# Grace.net
KiCad netlist of a schematic drawn in Altium Designer
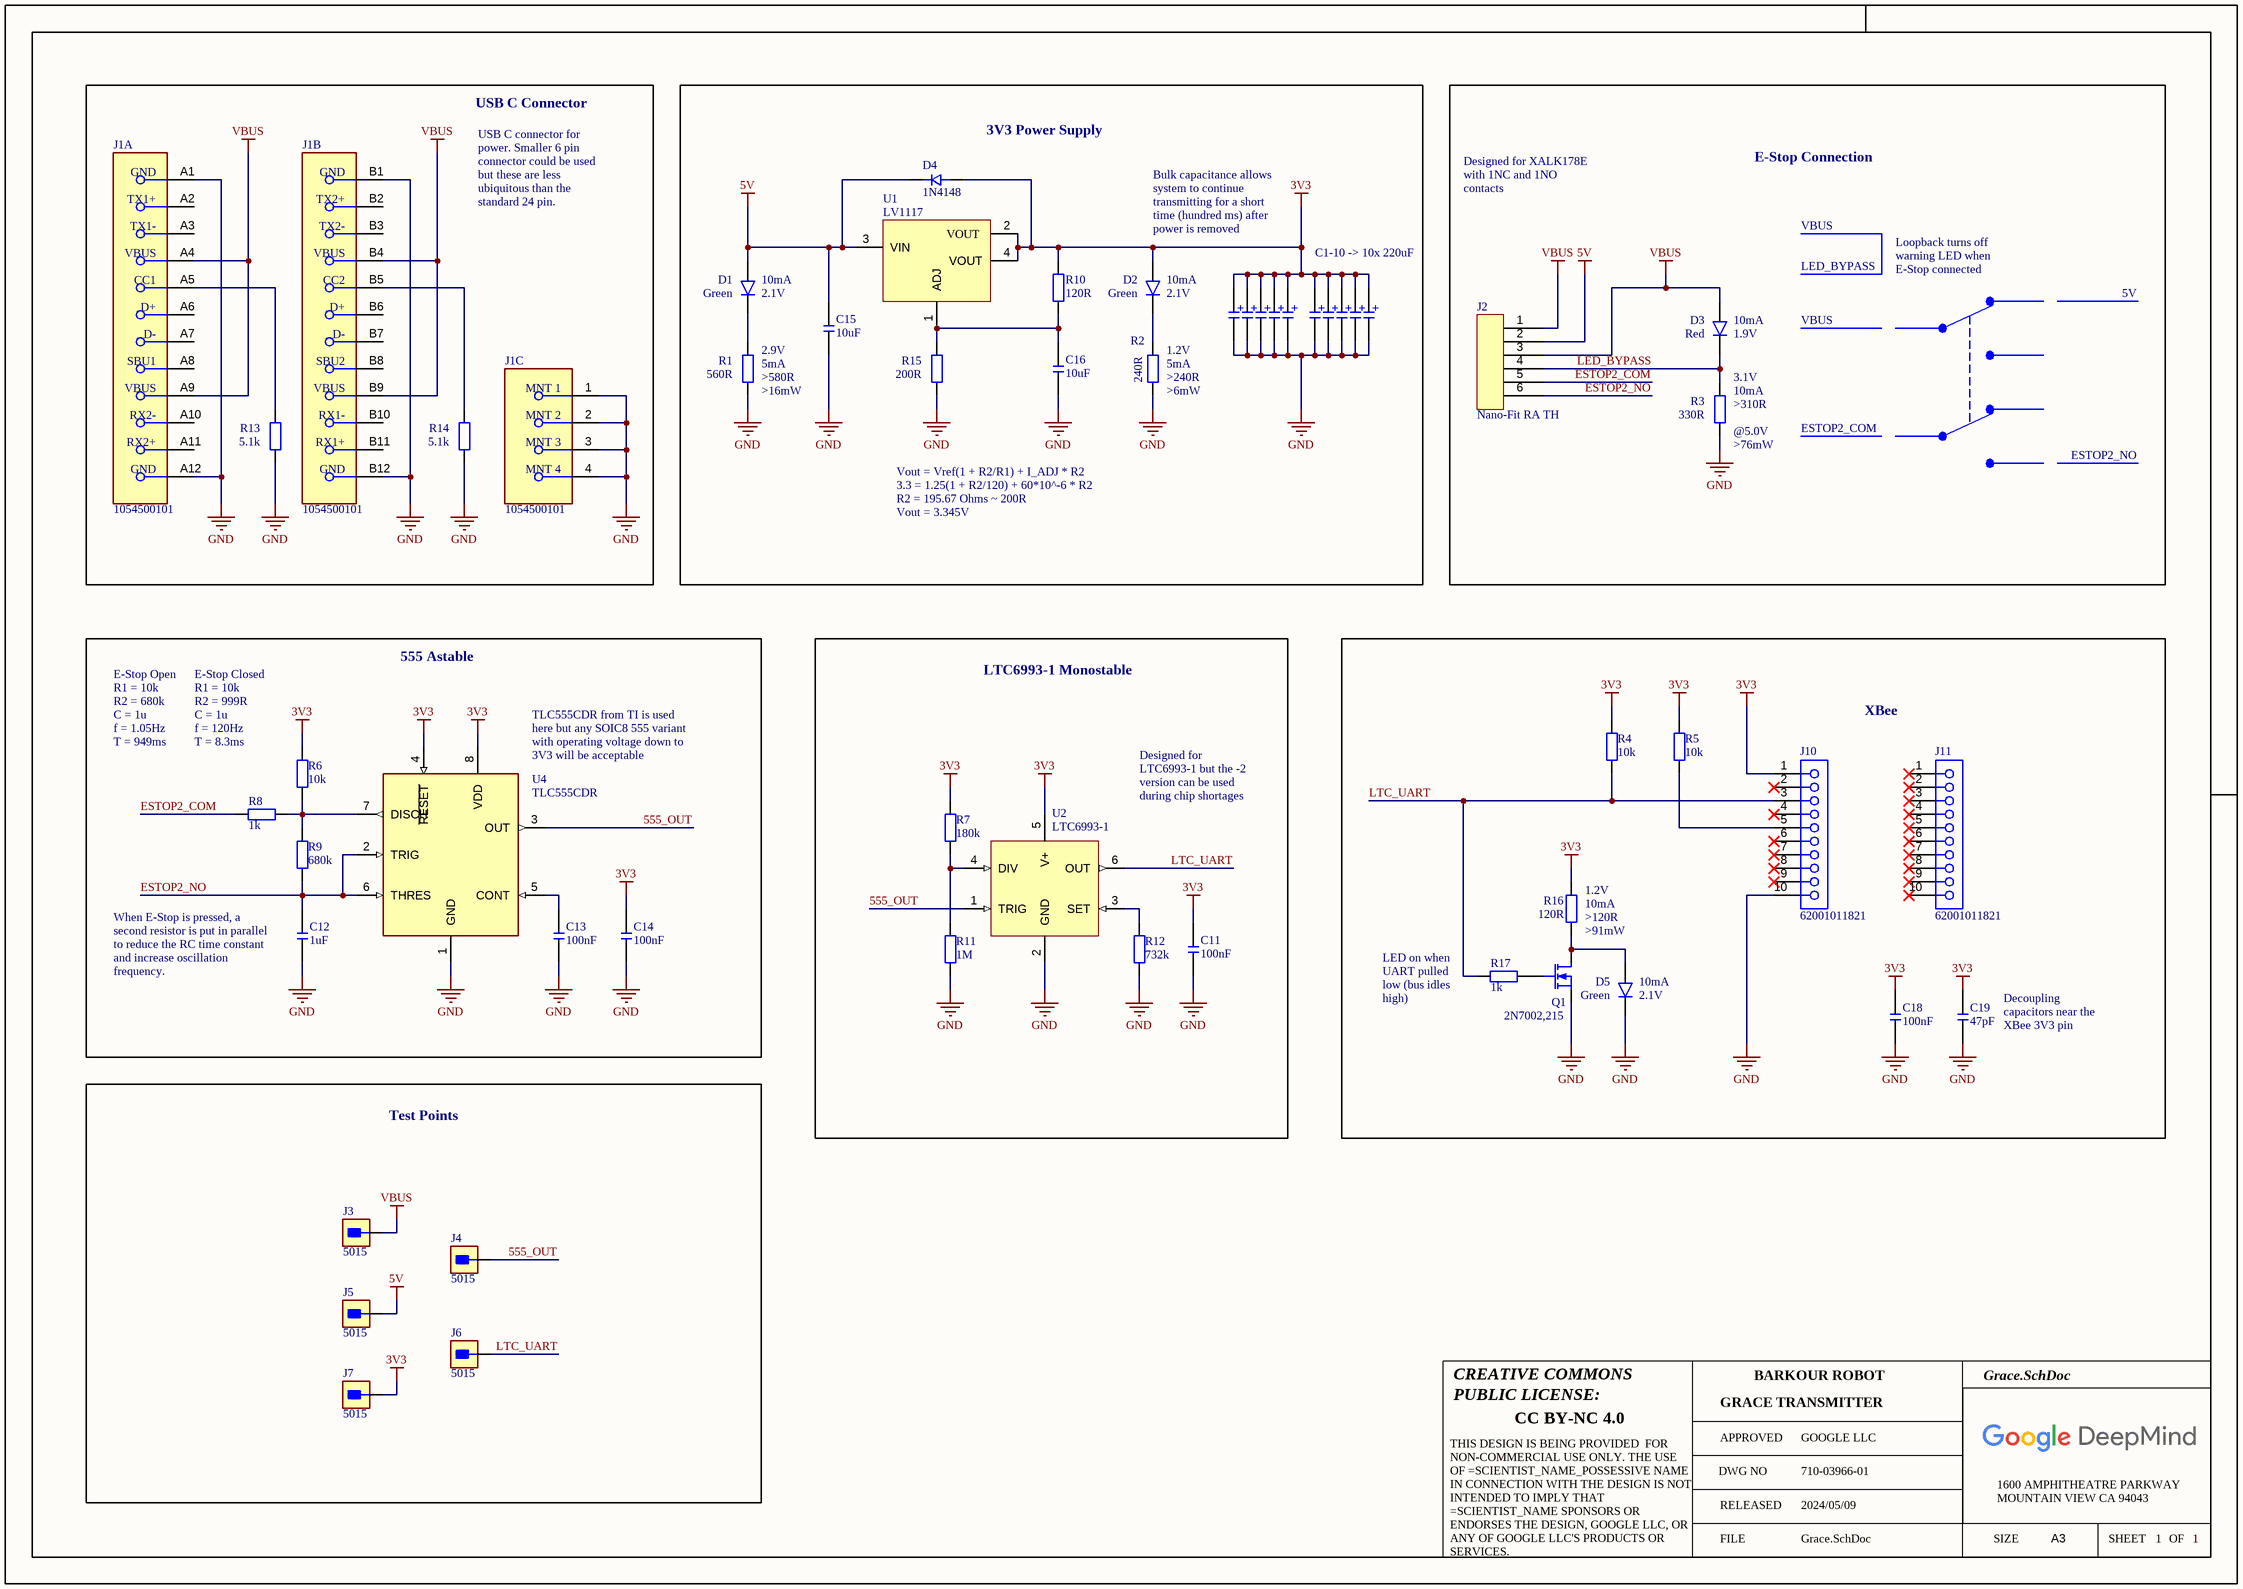
[diagram p0: Grace.SchDoc]

(export (version "E")
  (design (tool "Eeschema 10.0.6"))
  (components
    (comp (ref "C1")
      (value "220uF")
      (footprint "CAP ALSMD 6.6MM H7.7MM")
      (description "Polarised Capacitor")
      (fields (field (name "TOLERANCE") "20%"))
      (libsource (lib "DMR_common_lib") (part "C_POL"))
    )
    (comp (ref "C2")
      (value "220uF")
      (footprint "CAP ALSMD 6.6MM H7.7MM")
      (description "Polarised Capacitor")
      (fields (field (name "TOLERANCE") "20%"))
      (libsource (lib "DMR_common_lib") (part "C_POL"))
    )
    (comp (ref "C3")
      (value "220uF")
      (footprint "CAP ALSMD 6.6MM H7.7MM")
      (description "Polarised Capacitor")
      (fields (field (name "TOLERANCE") "20%"))
      (libsource (lib "DMR_common_lib") (part "C_POL"))
    )
    (comp (ref "C4")
      (value "220uF")
      (footprint "CAP ALSMD 6.6MM H7.7MM")
      (description "Polarised Capacitor")
      (fields (field (name "TOLERANCE") "20%"))
      (libsource (lib "DMR_common_lib") (part "C_POL"))
    )
    (comp (ref "C5")
      (value "220uF")
      (footprint "CAP ALSMD 6.6MM H7.7MM")
      (description "Polarised Capacitor")
      (fields (field (name "TOLERANCE") "20%"))
      (libsource (lib "DMR_common_lib") (part "C_POL"))
    )
    (comp (ref "C6")
      (value "220uF")
      (footprint "CAP ALSMD 6.6MM H7.7MM")
      (description "Polarised Capacitor")
      (fields (field (name "TOLERANCE") "20%"))
      (libsource (lib "DMR_common_lib") (part "C_POL"))
    )
    (comp (ref "C7")
      (value "220uF")
      (footprint "CAP ALSMD 6.6MM H7.7MM")
      (description "Polarised Capacitor")
      (fields (field (name "TOLERANCE") "20%"))
      (libsource (lib "DMR_common_lib") (part "C_POL"))
    )
    (comp (ref "C8")
      (value "220uF")
      (footprint "CAP ALSMD 6.6MM H7.7MM")
      (description "Polarised Capacitor")
      (fields (field (name "TOLERANCE") "20%"))
      (libsource (lib "DMR_common_lib") (part "C_POL"))
    )
    (comp (ref "C9")
      (value "220uF")
      (footprint "CAP ALSMD 6.6MM H7.7MM")
      (description "Polarised Capacitor")
      (fields (field (name "TOLERANCE") "20%"))
      (libsource (lib "DMR_common_lib") (part "C_POL"))
    )
    (comp (ref "C10")
      (value "220uF")
      (footprint "CAP ALSMD 6.6MM H7.7MM")
      (description "Polarised Capacitor")
      (fields (field (name "TOLERANCE") "20%"))
      (libsource (lib "DMR_common_lib") (part "C_POL"))
    )
    (comp (ref "C11")
      (value "100nF")
      (footprint "CAP 0603_1608 RF")
      (description "Capacitor")
      (fields (field (name "TOLERANCE") "20%"))
      (libsource (lib "DMR_common_lib") (part "C"))
    )
    (comp (ref "C12")
      (value "1uF")
      (footprint "CAP 0603_1608 RF")
      (description "Capacitor")
      (fields (field (name "TOLERANCE") "20%"))
      (libsource (lib "DMR_common_lib") (part "C"))
    )
    (comp (ref "C13")
      (value "100nF")
      (footprint "CAP 0603_1608 RF")
      (description "Capacitor")
      (fields (field (name "TOLERANCE") "20%"))
      (libsource (lib "DMR_common_lib") (part "C"))
    )
    (comp (ref "C14")
      (value "100nF")
      (footprint "CAP 0603_1608 RF")
      (description "Capacitor")
      (fields (field (name "TOLERANCE") "20%"))
      (libsource (lib "DMR_common_lib") (part "C"))
    )
    (comp (ref "C15")
      (value "10uF")
      (footprint "CAP 1206_3216")
      (description "Generic Capacitor")
      (fields (field (name "TOLERANCE") "10%"))
      (libsource (lib "DMR_common_lib") (part "C"))
    )
    (comp (ref "C16")
      (value "10uF")
      (footprint "CAP 1206_3216")
      (description "Generic Capacitor")
      (fields (field (name "TOLERANCE") "10%"))
      (libsource (lib "DMR_common_lib") (part "C"))
    )
    (comp (ref "C18")
      (value "100nF")
      (footprint "CAP 0603_1608 RF")
      (description "Capacitor")
      (fields (field (name "TOLERANCE") "20%"))
      (libsource (lib "DMR_common_lib") (part "C"))
    )
    (comp (ref "C19")
      (value "47pF")
      (footprint "CAP 0603_1608 RF")
      (description "Capacitor")
      (fields (field (name "TOLERANCE") "20%"))
      (libsource (lib "DMR_common_lib") (part "C"))
    )
    (comp (ref "D1")
      (value "HLMP-3507")
      (footprint "LED TH 5mm")
      (description "Green 5mm TH LED, T-1 3/4, 10mA Ic, 2.1V")
      (fields
        (field (name "FORWARD CURRENT") "10mA")
        (field (name "FORWARD VOLTAGE") "2.1V")
        (field (name "COLOUR") "Green")
      )
      (libsource (lib "DMR_common_lib") (part "LED_TH5_GREEN"))
    )
    (comp (ref "D2")
      (value "HLMP-3507")
      (footprint "LED TH 5mm")
      (description "Green 5mm TH LED, T-1 3/4, 10mA Ic, 2.1V")
      (fields
        (field (name "FORWARD CURRENT") "10mA")
        (field (name "FORWARD VOLTAGE") "2.1V")
        (field (name "COLOUR") "Green")
      )
      (libsource (lib "DMR_common_lib") (part "LED_TH5_GREEN"))
    )
    (comp (ref "D3")
      (value "HLMP-3301")
      (footprint "LED TH 5mm")
      (description "Red 5mm TH LED, T-1 3/4, 10mA Ic, 1.9V")
      (fields
        (field (name "FORWARD CURRENT") "10mA")
        (field (name "FORWARD VOLTAGE") "1.9V")
        (field (name "COLOUR") "Red")
      )
      (libsource (lib "DMR_common_lib") (part "LED_TH5_RED"))
    )
    (comp (ref "D4")
      (value "1N4148WS-7-F")
      (footprint "SOD323")
      (description "Signal Diode VR=75V IF=150mA Trr=4ns P=200mW")
      (fields
        (field (name "MANUFACTURER") "Diodes")
        (field (name "VOLTAGE") "75V")
        (field (name "COLLOQUIAL") "1N4148")
      )
      (libsource (lib "DMR_common_lib") (part "1N4148"))
    )
    (comp (ref "D5")
      (value "HLMP-3507")
      (footprint "LED TH 5mm")
      (description "Green 5mm TH LED, T-1 3/4, 10mA Ic, 2.1V")
      (fields
        (field (name "FORWARD CURRENT") "10mA")
        (field (name "FORWARD VOLTAGE") "2.1V")
        (field (name "COLOUR") "Green")
      )
      (libsource (lib "DMR_common_lib") (part "LED_TH5_GREEN"))
    )
    (comp (ref "J1")
      (value "1054500101")
      (footprint "Molex 1054500101 - With Model")
      (description "Conn USB 3.1 Type C F 24 POS Solder RA SMD 24 Terminal 1 Port USB 3.1 T/R")
      (fields
        (field (name "MANUFACTURER") "Molex")
        (field (name "OCTOPART") "https://octopart.com/105450-0101-molex-68082325")
      )
      (libsource (lib "DMR_common_lib") (part "1054500101"))
    )
    (comp (ref "J2")
      (value "105313-1206")
      (footprint "MOLEX 1053131106")
      (description "Nano-Fit Right Angle Header; Through Hole; 2.50mm; Single Row; 6 Circuit; Gold Plated")
      (fields (field (name "MANUFACTURER") "Molex") (field (name "COLLOQUIAL") "Nano-Fit RA TH"))
      (libsource (lib "DMR_common_lib") (part "Nano-Fit RA TH 6 Way Header"))
    )
    (comp (ref "J3")
      (value "5015")
      (footprint "FP-5015-MFG-RF")
      (description "PC TEST POINT MINIATURE")
      (fields
        (field (name "MANUFACTURER") "keystone")
        (field (name "OCTOPART") "https://octopart.com/5015-keystone-3822")
      )
      (libsource (lib "DMR_common_lib") (part "5015"))
    )
    (comp (ref "J4")
      (value "5015")
      (footprint "FP-5015-MFG-RF")
      (description "PC TEST POINT MINIATURE")
      (fields
        (field (name "MANUFACTURER") "keystone")
        (field (name "OCTOPART") "https://octopart.com/5015-keystone-3822")
      )
      (libsource (lib "DMR_common_lib") (part "5015"))
    )
    (comp (ref "J5")
      (value "5015")
      (footprint "FP-5015-MFG-RF")
      (description "PC TEST POINT MINIATURE")
      (fields
        (field (name "MANUFACTURER") "keystone")
        (field (name "OCTOPART") "https://octopart.com/5015-keystone-3822")
      )
      (libsource (lib "DMR_common_lib") (part "5015"))
    )
    (comp (ref "J6")
      (value "5015")
      (footprint "FP-5015-MFG-RF")
      (description "PC TEST POINT MINIATURE")
      (fields
        (field (name "MANUFACTURER") "keystone")
        (field (name "OCTOPART") "https://octopart.com/5015-keystone-3822")
      )
      (libsource (lib "DMR_common_lib") (part "5015"))
    )
    (comp (ref "J7")
      (value "5015")
      (footprint "FP-5015-MFG-RF")
      (description "PC TEST POINT MINIATURE")
      (fields
        (field (name "MANUFACTURER") "keystone")
        (field (name "OCTOPART") "https://octopart.com/5015-keystone-3822")
      )
      (libsource (lib "DMR_common_lib") (part "5015"))
    )
    (comp (ref "J10")
      (value "62001011821")
      (footprint "62001011821")
      (libsource (lib "Altium Content Vault") (part "Header_Female_1R_10P"))
    )
    (comp (ref "J11")
      (value "62001011821")
      (footprint "62001011821")
      (libsource (lib "Altium Content Vault") (part "Header_Female_1R_10P"))
    )
    (comp (ref "Q1")
      (value "2N7002,215")
      (footprint "NEXPERIA SOT-23-3")
      (description "MOSFET N-CH 60V 300MA SOT-23")
      (fields (field (name "MANUFACTURER") "Nexperia"))
      (libsource (lib "DMR_common_lib") (part "2N7002"))
    )
    (comp (ref "R1")
      (value "560R")
      (footprint "RES 0603_1608 RF")
      (description "Resistor")
      (fields (field (name "TOLERANCE") "1%"))
      (libsource (lib "DMR_common_lib") (part "R"))
    )
    (comp (ref "R2")
      (value "240R")
      (footprint "RES 0603_1608 RF")
      (description "Resistor")
      (fields (field (name "TOLERANCE") "1%"))
      (libsource (lib "DMR_common_lib") (part "R"))
    )
    (comp (ref "R3")
      (value "330R")
      (footprint "RES 0603_1608 RF")
      (description "Resistor")
      (fields (field (name "TOLERANCE") "1%"))
      (libsource (lib "DMR_common_lib") (part "R"))
    )
    (comp (ref "R4")
      (value "10k")
      (footprint "RES 0603_1608 RF")
      (description "Resistor")
      (fields (field (name "TOLERANCE") "1%"))
      (libsource (lib "DMR_common_lib") (part "R"))
    )
    (comp (ref "R5")
      (value "10k")
      (footprint "RES 0603_1608 RF")
      (description "Resistor")
      (fields (field (name "TOLERANCE") "1%"))
      (libsource (lib "DMR_common_lib") (part "R"))
    )
    (comp (ref "R6")
      (value "10k")
      (footprint "RES 0603_1608 RF")
      (description "Resistor")
      (fields (field (name "TOLERANCE") "1%"))
      (libsource (lib "DMR_common_lib") (part "R"))
    )
    (comp (ref "R7")
      (value "180k")
      (footprint "RES 0603_1608 RF")
      (description "Resistor")
      (fields (field (name "TOLERANCE") "1%"))
      (libsource (lib "DMR_common_lib") (part "R"))
    )
    (comp (ref "R8")
      (value "1k")
      (footprint "RES 0603_1608 RF")
      (description "Resistor")
      (fields (field (name "TOLERANCE") "1%"))
      (libsource (lib "") (part "R_1"))
    )
    (comp (ref "R9")
      (value "680k")
      (footprint "RES 0603_1608 RF")
      (description "Resistor")
      (fields (field (name "TOLERANCE") "1%"))
      (libsource (lib "DMR_common_lib") (part "R"))
    )
    (comp (ref "R10")
      (value "120R")
      (footprint "RES 1206_3216 RF")
      (description "Resistor")
      (fields (field (name "TOLERANCE") "1%"))
      (libsource (lib "DMR_common_lib") (part "R"))
    )
    (comp (ref "R11")
      (value "1M")
      (footprint "RES 0603_1608 RF")
      (description "Resistor")
      (fields (field (name "TOLERANCE") "1%"))
      (libsource (lib "DMR_common_lib") (part "R"))
    )
    (comp (ref "R12")
      (value "732k")
      (footprint "RES 0603_1608 RF")
      (description "Resistor")
      (fields (field (name "TOLERANCE") "1%"))
      (libsource (lib "DMR_common_lib") (part "R"))
    )
    (comp (ref "R13")
      (value "5.1k")
      (footprint "RES 0603_1608 RF")
      (description "Resistor")
      (fields (field (name "TOLERANCE") "1%"))
      (libsource (lib "DMR_common_lib") (part "R"))
    )
    (comp (ref "R14")
      (value "5.1k")
      (footprint "RES 0603_1608 RF")
      (description "Resistor")
      (fields (field (name "TOLERANCE") "1%"))
      (libsource (lib "DMR_common_lib") (part "R"))
    )
    (comp (ref "R15")
      (value "200R")
      (footprint "RES 1206_3216 RF")
      (description "Resistor")
      (fields (field (name "TOLERANCE") "1%"))
      (libsource (lib "DMR_common_lib") (part "R"))
    )
    (comp (ref "R16")
      (value "120R")
      (footprint "RES 1206_3216 RF")
      (description "Resistor")
      (fields (field (name "TOLERANCE") "1%"))
      (libsource (lib "DMR_common_lib") (part "R"))
    )
    (comp (ref "R17")
      (value "1k")
      (footprint "RES 0603_1608 RF")
      (description "Resistor")
      (fields (field (name "TOLERANCE") "1%"))
      (libsource (lib "") (part "R_1"))
    )
    (comp (ref "U1")
      (value "TLV1117CDCY")
      (footprint "TI SOT-223 DCY")
      (description "LV1117 type LDO Regulator Pos 1.25V to 13.7V 0.8A 4-Pin(3+Tab) SOT-223 Tube")
      (fields (field (name "MANUFACTURER") "Texas Instruments") (field (name "COLLOQUIAL") "LV1117"))
      (libsource (lib "DMR_common_lib") (part "TLV1117CDCY"))
    )
    (comp (ref "U2")
      (value "LTC6993CS6-1#TRMPBF")
      (footprint "LT TSOT-23-6 S6")
      (fields (field (name "MANUFACTURER") "Linear Technology") (field (name "COLLOQUIAL") "LTC6993-1"))
      (libsource (lib "DMR_common_lib") (part "LTC6993-1"))
    )
    (comp (ref "U4")
      (value "TLC555CDR")
      (footprint "TI SOIC-8 D0008A")
      (description "2.1-MHz, 250-µA, Low-Power Timer 8-SOIC 0 to 70")
      (libsource (lib "DMR_common_lib") (part "TLC555CDR"))
    )
  )
  (nets
    (net (code "1") (name "/555_OUT") (class "Default")
      (node (ref "J4") (pin "1") (pinfunction "1_1") (pintype "passive"))
      (node (ref "U2") (pin "1") (pinfunction "TRIG_1") (pintype "input"))
      (node (ref "U4") (pin "3") (pinfunction "OUT_3") (pintype "output"))
    )
    (net (code "2") (name "/ESTOP2_COM") (class "Default")
      (node (ref "J2") (pin "5") (pintype "passive"))
      (node (ref "R8") (pin "1") (pinfunction "1_1") (pintype "passive"))
    )
    (net (code "3") (name "/ESTOP2_NO") (class "Default")
      (node (ref "C12") (pin "2") (pinfunction "2_2") (pintype "passive"))
      (node (ref "J2") (pin "6") (pintype "passive"))
      (node (ref "R9") (pin "1") (pinfunction "1_1") (pintype "passive"))
      (node (ref "U4") (pin "2") (pinfunction "TRIG_2") (pintype "input"))
      (node (ref "U4") (pin "6") (pinfunction "THRES_6") (pintype "input"))
    )
    (net (code "4") (name "/LED_BYPASS") (class "Default")
      (node (ref "D3") (pin "1") (pinfunction "Cathode_1") (pintype "passive"))
      (node (ref "J2") (pin "4") (pintype "passive"))
      (node (ref "R3") (pin "2") (pinfunction "2_2") (pintype "passive"))
    )
    (net (code "5") (name "/LTC_UART") (class "Default")
      (node (ref "J10") (pin "3") (pinfunction "3_3") (pintype "passive"))
      (node (ref "J6") (pin "1") (pinfunction "1_1") (pintype "passive"))
      (node (ref "R17") (pin "1") (pinfunction "1_1") (pintype "passive"))
      (node (ref "R4") (pin "1") (pinfunction "1_1") (pintype "passive"))
      (node (ref "U2") (pin "6") (pinfunction "OUT_6") (pintype "output"))
    )
    (net (code "6") (name "3V3") (class "Default")
      (node (ref "C1") (pin "1") (pinfunction "1_1") (pintype "passive"))
      (node (ref "C10") (pin "1") (pinfunction "1_1") (pintype "passive"))
      (node (ref "C11") (pin "2") (pinfunction "2_2") (pintype "passive"))
      (node (ref "C14") (pin "2") (pinfunction "2_2") (pintype "passive"))
      (node (ref "C18") (pin "2") (pinfunction "2_2") (pintype "passive"))
      (node (ref "C19") (pin "2") (pinfunction "2_2") (pintype "passive"))
      (node (ref "C2") (pin "1") (pinfunction "1_1") (pintype "passive"))
      (node (ref "C3") (pin "1") (pinfunction "1_1") (pintype "passive"))
      (node (ref "C4") (pin "1") (pinfunction "1_1") (pintype "passive"))
      (node (ref "C5") (pin "1") (pinfunction "1_1") (pintype "passive"))
      (node (ref "C6") (pin "1") (pinfunction "1_1") (pintype "passive"))
      (node (ref "C7") (pin "1") (pinfunction "1_1") (pintype "passive"))
      (node (ref "C8") (pin "1") (pinfunction "1_1") (pintype "passive"))
      (node (ref "C9") (pin "1") (pinfunction "1_1") (pintype "passive"))
      (node (ref "D2") (pin "2") (pinfunction "Anode_2") (pintype "passive"))
      (node (ref "D4") (pin "1") (pinfunction "1_1") (pintype "passive"))
      (node (ref "J10") (pin "1") (pinfunction "1_1") (pintype "passive"))
      (node (ref "J7") (pin "1") (pinfunction "1_1") (pintype "passive"))
      (node (ref "R10") (pin "2") (pinfunction "2_2") (pintype "passive"))
      (node (ref "R16") (pin "2") (pinfunction "2_2") (pintype "passive"))
      (node (ref "R4") (pin "2") (pinfunction "2_2") (pintype "passive"))
      (node (ref "R5") (pin "2") (pinfunction "2_2") (pintype "passive"))
      (node (ref "R6") (pin "2") (pinfunction "2_2") (pintype "passive"))
      (node (ref "R7") (pin "2") (pinfunction "2_2") (pintype "passive"))
      (node (ref "U1") (pin "2") (pinfunction "VOUT_2") (pintype "power_in"))
      (node (ref "U1") (pin "4") (pinfunction "VOUT_4") (pintype "power_in"))
      (node (ref "U2") (pin "5") (pinfunction "V+_5") (pintype "power_in"))
      (node (ref "U4") (pin "4") (pinfunction "~{RESET}_4") (pintype "input"))
      (node (ref "U4") (pin "8") (pinfunction "VDD_8") (pintype "power_in"))
    )
    (net (code "7") (name "5V") (class "Default")
      (node (ref "C15") (pin "2") (pinfunction "2_2") (pintype "passive"))
      (node (ref "D1") (pin "2") (pinfunction "Anode_2") (pintype "passive"))
      (node (ref "D4") (pin "2") (pinfunction "2_2") (pintype "passive"))
      (node (ref "J2") (pin "2") (pintype "passive"))
      (node (ref "J5") (pin "1") (pinfunction "1_1") (pintype "passive"))
      (node (ref "U1") (pin "3") (pinfunction "VIN_3") (pintype "power_in"))
    )
    (net (code "8") (name "GND") (class "Default")
      (node (ref "C1") (pin "2") (pinfunction "2_2") (pintype "passive"))
      (node (ref "C10") (pin "2") (pinfunction "2_2") (pintype "passive"))
      (node (ref "C11") (pin "1") (pinfunction "1_1") (pintype "passive"))
      (node (ref "C12") (pin "1") (pinfunction "1_1") (pintype "passive"))
      (node (ref "C13") (pin "1") (pinfunction "1_1") (pintype "passive"))
      (node (ref "C14") (pin "1") (pinfunction "1_1") (pintype "passive"))
      (node (ref "C15") (pin "1") (pinfunction "1_1") (pintype "passive"))
      (node (ref "C16") (pin "1") (pinfunction "1_1") (pintype "passive"))
      (node (ref "C18") (pin "1") (pinfunction "1_1") (pintype "passive"))
      (node (ref "C19") (pin "1") (pinfunction "1_1") (pintype "passive"))
      (node (ref "C2") (pin "2") (pinfunction "2_2") (pintype "passive"))
      (node (ref "C3") (pin "2") (pinfunction "2_2") (pintype "passive"))
      (node (ref "C4") (pin "2") (pinfunction "2_2") (pintype "passive"))
      (node (ref "C5") (pin "2") (pinfunction "2_2") (pintype "passive"))
      (node (ref "C6") (pin "2") (pinfunction "2_2") (pintype "passive"))
      (node (ref "C7") (pin "2") (pinfunction "2_2") (pintype "passive"))
      (node (ref "C8") (pin "2") (pinfunction "2_2") (pintype "passive"))
      (node (ref "C9") (pin "2") (pinfunction "2_2") (pintype "passive"))
      (node (ref "D5") (pin "1") (pinfunction "Cathode_1") (pintype "passive"))
      (node (ref "J1") (pin "1") (pinfunction "MNT_1_1") (pintype "passive"))
      (node (ref "J1") (pin "2") (pinfunction "MNT_2_2") (pintype "passive"))
      (node (ref "J1") (pin "3") (pinfunction "MNT_3_3") (pintype "passive"))
      (node (ref "J1") (pin "4") (pinfunction "MNT_4_4") (pintype "passive"))
      (node (ref "J1") (pin "A1") (pinfunction "GND_A1") (pintype "passive"))
      (node (ref "J1") (pin "A12") (pinfunction "GND_A12") (pintype "passive"))
      (node (ref "J1") (pin "B1") (pinfunction "GND_B1") (pintype "passive"))
      (node (ref "J1") (pin "B12") (pinfunction "GND_B12") (pintype "passive"))
      (node (ref "J10") (pin "10") (pinfunction "10_10") (pintype "passive"))
      (node (ref "Q1") (pin "2") (pinfunction "S_2") (pintype "passive"))
      (node (ref "R1") (pin "1") (pinfunction "1_1") (pintype "passive"))
      (node (ref "R11") (pin "1") (pinfunction "1_1") (pintype "passive"))
      (node (ref "R12") (pin "1") (pinfunction "1_1") (pintype "passive"))
      (node (ref "R13") (pin "1") (pinfunction "1_1") (pintype "passive"))
      (node (ref "R14") (pin "1") (pinfunction "1_1") (pintype "passive"))
      (node (ref "R15") (pin "1") (pinfunction "1_1") (pintype "passive"))
      (node (ref "R2") (pin "1") (pinfunction "1_1") (pintype "passive"))
      (node (ref "R3") (pin "1") (pinfunction "1_1") (pintype "passive"))
      (node (ref "U2") (pin "2") (pinfunction "GND_2") (pintype "power_in"))
      (node (ref "U4") (pin "1") (pinfunction "GND_1") (pintype "power_in"))
    )
    (net (code "9") (name "Net-(D1-Cathode)") (class "Default")
      (node (ref "D1") (pin "1") (pinfunction "Cathode_1") (pintype "passive"))
      (node (ref "R1") (pin "2") (pinfunction "2_2") (pintype "passive"))
    )
    (net (code "10") (name "Net-(D2-Cathode)") (class "Default")
      (node (ref "D2") (pin "1") (pinfunction "Cathode_1") (pintype "passive"))
      (node (ref "R2") (pin "2") (pinfunction "2_2") (pintype "passive"))
    )
    (net (code "11") (name "Net-(D5-Anode)") (class "Default")
      (node (ref "D5") (pin "2") (pinfunction "Anode_2") (pintype "passive"))
      (node (ref "Q1") (pin "3") (pinfunction "D_3") (pintype "passive"))
      (node (ref "R16") (pin "1") (pinfunction "1_1") (pintype "passive"))
    )
    (net (code "12") (name "Net-(J1A-CC1)") (class "Default")
      (node (ref "J1") (pin "A5") (pinfunction "CC1_A5") (pintype "passive"))
      (node (ref "R13") (pin "2") (pinfunction "2_2") (pintype "passive"))
    )
    (net (code "13") (name "Net-(J1B-CC2)") (class "Default")
      (node (ref "J1") (pin "B5") (pinfunction "CC2_B5") (pintype "passive"))
      (node (ref "R14") (pin "2") (pinfunction "2_2") (pintype "passive"))
    )
    (net (code "14") (name "Net-(J10-Pad5)") (class "Default")
      (node (ref "J10") (pin "5") (pinfunction "5_5") (pintype "passive"))
      (node (ref "R5") (pin "1") (pinfunction "1_1") (pintype "passive"))
    )
    (net (code "15") (name "Net-(Q1-G)") (class "Default")
      (node (ref "Q1") (pin "1") (pinfunction "G_1") (pintype "passive"))
      (node (ref "R17") (pin "2") (pinfunction "2_2") (pintype "passive"))
    )
    (net (code "16") (name "Net-(U1-ADJ)") (class "Default")
      (node (ref "C16") (pin "2") (pinfunction "2_2") (pintype "passive"))
      (node (ref "R10") (pin "1") (pinfunction "1_1") (pintype "passive"))
      (node (ref "R15") (pin "2") (pinfunction "2_2") (pintype "passive"))
      (node (ref "U1") (pin "1") (pinfunction "ADJ_1") (pintype "power_in"))
    )
    (net (code "17") (name "Net-(U2-DIV)") (class "Default")
      (node (ref "R11") (pin "2") (pinfunction "2_2") (pintype "passive"))
      (node (ref "R7") (pin "1") (pinfunction "1_1") (pintype "passive"))
      (node (ref "U2") (pin "4") (pinfunction "DIV_4") (pintype "input"))
    )
    (net (code "18") (name "Net-(U2-SET)") (class "Default")
      (node (ref "R12") (pin "2") (pinfunction "2_2") (pintype "passive"))
      (node (ref "U2") (pin "3") (pinfunction "SET_3") (pintype "input"))
    )
    (net (code "19") (name "Net-(U4-CONT)") (class "Default")
      (node (ref "C13") (pin "2") (pinfunction "2_2") (pintype "passive"))
      (node (ref "U4") (pin "5") (pinfunction "CONT_5") (pintype "input"))
    )
    (net (code "20") (name "Net-(U4-DISCH)") (class "Default")
      (node (ref "R6") (pin "1") (pinfunction "1_1") (pintype "passive"))
      (node (ref "R8") (pin "2") (pinfunction "2_2") (pintype "passive"))
      (node (ref "R9") (pin "2") (pinfunction "2_2") (pintype "passive"))
      (node (ref "U4") (pin "7") (pinfunction "DISCH_7") (pintype "output"))
    )
    (net (code "21") (name "VBUS") (class "Default")
      (node (ref "D3") (pin "2") (pinfunction "Anode_2") (pintype "passive"))
      (node (ref "J1") (pin "A4") (pinfunction "VBUS_A4") (pintype "passive"))
      (node (ref "J1") (pin "A9") (pinfunction "VBUS_A9") (pintype "passive"))
      (node (ref "J1") (pin "B4") (pinfunction "VBUS_B4") (pintype "passive"))
      (node (ref "J1") (pin "B9") (pinfunction "VBUS_B9") (pintype "passive"))
      (node (ref "J2") (pin "1") (pintype "passive"))
      (node (ref "J2") (pin "3") (pintype "passive"))
      (node (ref "J3") (pin "1") (pinfunction "1_1") (pintype "passive"))
    )
    (net (code "22") (name "unconnected-(J1A-D+-PadA6)") (class "Default")
      (node (ref "J1") (pin "A6") (pinfunction "D+_A6") (pintype "passive"))
    )
    (net (code "23") (name "unconnected-(J1A-D--PadA7)") (class "Default")
      (node (ref "J1") (pin "A7") (pinfunction "D-_A7") (pintype "passive"))
    )
    (net (code "24") (name "unconnected-(J1A-RX2+-PadA11)") (class "Default")
      (node (ref "J1") (pin "A11") (pinfunction "RX2+_A11") (pintype "passive"))
    )
    (net (code "25") (name "unconnected-(J1A-RX2--PadA10)") (class "Default")
      (node (ref "J1") (pin "A10") (pinfunction "RX2-_A10") (pintype "passive"))
    )
    (net (code "26") (name "unconnected-(J1A-SBU1-PadA8)") (class "Default")
      (node (ref "J1") (pin "A8") (pinfunction "SBU1_A8") (pintype "passive"))
    )
    (net (code "27") (name "unconnected-(J1A-TX1+-PadA2)") (class "Default")
      (node (ref "J1") (pin "A2") (pinfunction "TX1+_A2") (pintype "passive"))
    )
    (net (code "28") (name "unconnected-(J1A-TX1--PadA3)") (class "Default")
      (node (ref "J1") (pin "A3") (pinfunction "TX1-_A3") (pintype "passive"))
    )
    (net (code "29") (name "unconnected-(J1B-D+-PadB6)") (class "Default")
      (node (ref "J1") (pin "B6") (pinfunction "D+_B6") (pintype "passive"))
    )
    (net (code "30") (name "unconnected-(J1B-D--PadB7)") (class "Default")
      (node (ref "J1") (pin "B7") (pinfunction "D-_B7") (pintype "passive"))
    )
    (net (code "31") (name "unconnected-(J1B-RX1+-PadB11)") (class "Default")
      (node (ref "J1") (pin "B11") (pinfunction "RX1+_B11") (pintype "passive"))
    )
    (net (code "32") (name "unconnected-(J1B-RX1--PadB10)") (class "Default")
      (node (ref "J1") (pin "B10") (pinfunction "RX1-_B10") (pintype "passive"))
    )
    (net (code "33") (name "unconnected-(J1B-SBU2-PadB8)") (class "Default")
      (node (ref "J1") (pin "B8") (pinfunction "SBU2_B8") (pintype "passive"))
    )
    (net (code "34") (name "unconnected-(J1B-TX2+-PadB2)") (class "Default")
      (node (ref "J1") (pin "B2") (pinfunction "TX2+_B2") (pintype "passive"))
    )
    (net (code "35") (name "unconnected-(J1B-TX2--PadB3)") (class "Default")
      (node (ref "J1") (pin "B3") (pinfunction "TX2-_B3") (pintype "passive"))
    )
    (net (code "36") (name "unconnected-(J10-Pad2)") (class "Default")
      (node (ref "J10") (pin "2") (pinfunction "2_2") (pintype "passive+no_connect"))
    )
    (net (code "37") (name "unconnected-(J10-Pad4)") (class "Default")
      (node (ref "J10") (pin "4") (pinfunction "4_4") (pintype "passive+no_connect"))
    )
    (net (code "38") (name "unconnected-(J10-Pad6)") (class "Default")
      (node (ref "J10") (pin "6") (pinfunction "6_6") (pintype "passive+no_connect"))
    )
    (net (code "39") (name "unconnected-(J10-Pad7)") (class "Default")
      (node (ref "J10") (pin "7") (pinfunction "7_7") (pintype "passive+no_connect"))
    )
    (net (code "40") (name "unconnected-(J10-Pad8)") (class "Default")
      (node (ref "J10") (pin "8") (pinfunction "8_8") (pintype "passive+no_connect"))
    )
    (net (code "41") (name "unconnected-(J10-Pad9)") (class "Default")
      (node (ref "J10") (pin "9") (pinfunction "9_9") (pintype "passive+no_connect"))
    )
    (net (code "42") (name "unconnected-(J11-Pad1)") (class "Default")
      (node (ref "J11") (pin "1") (pinfunction "1_1") (pintype "passive+no_connect"))
    )
    (net (code "43") (name "unconnected-(J11-Pad2)") (class "Default")
      (node (ref "J11") (pin "2") (pinfunction "2_2") (pintype "passive+no_connect"))
    )
    (net (code "44") (name "unconnected-(J11-Pad3)") (class "Default")
      (node (ref "J11") (pin "3") (pinfunction "3_3") (pintype "passive+no_connect"))
    )
    (net (code "45") (name "unconnected-(J11-Pad4)") (class "Default")
      (node (ref "J11") (pin "4") (pinfunction "4_4") (pintype "passive+no_connect"))
    )
    (net (code "46") (name "unconnected-(J11-Pad5)") (class "Default")
      (node (ref "J11") (pin "5") (pinfunction "5_5") (pintype "passive+no_connect"))
    )
    (net (code "47") (name "unconnected-(J11-Pad6)") (class "Default")
      (node (ref "J11") (pin "6") (pinfunction "6_6") (pintype "passive+no_connect"))
    )
    (net (code "48") (name "unconnected-(J11-Pad7)") (class "Default")
      (node (ref "J11") (pin "7") (pinfunction "7_7") (pintype "passive+no_connect"))
    )
    (net (code "49") (name "unconnected-(J11-Pad8)") (class "Default")
      (node (ref "J11") (pin "8") (pinfunction "8_8") (pintype "passive+no_connect"))
    )
    (net (code "50") (name "unconnected-(J11-Pad9)") (class "Default")
      (node (ref "J11") (pin "9") (pinfunction "9_9") (pintype "passive+no_connect"))
    )
    (net (code "51") (name "unconnected-(J11-Pad10)") (class "Default")
      (node (ref "J11") (pin "10") (pinfunction "10_10") (pintype "passive+no_connect"))
    )
  )
)
